# peripherals.net
KiCad netlist of a schematic drawn in Altium Designer
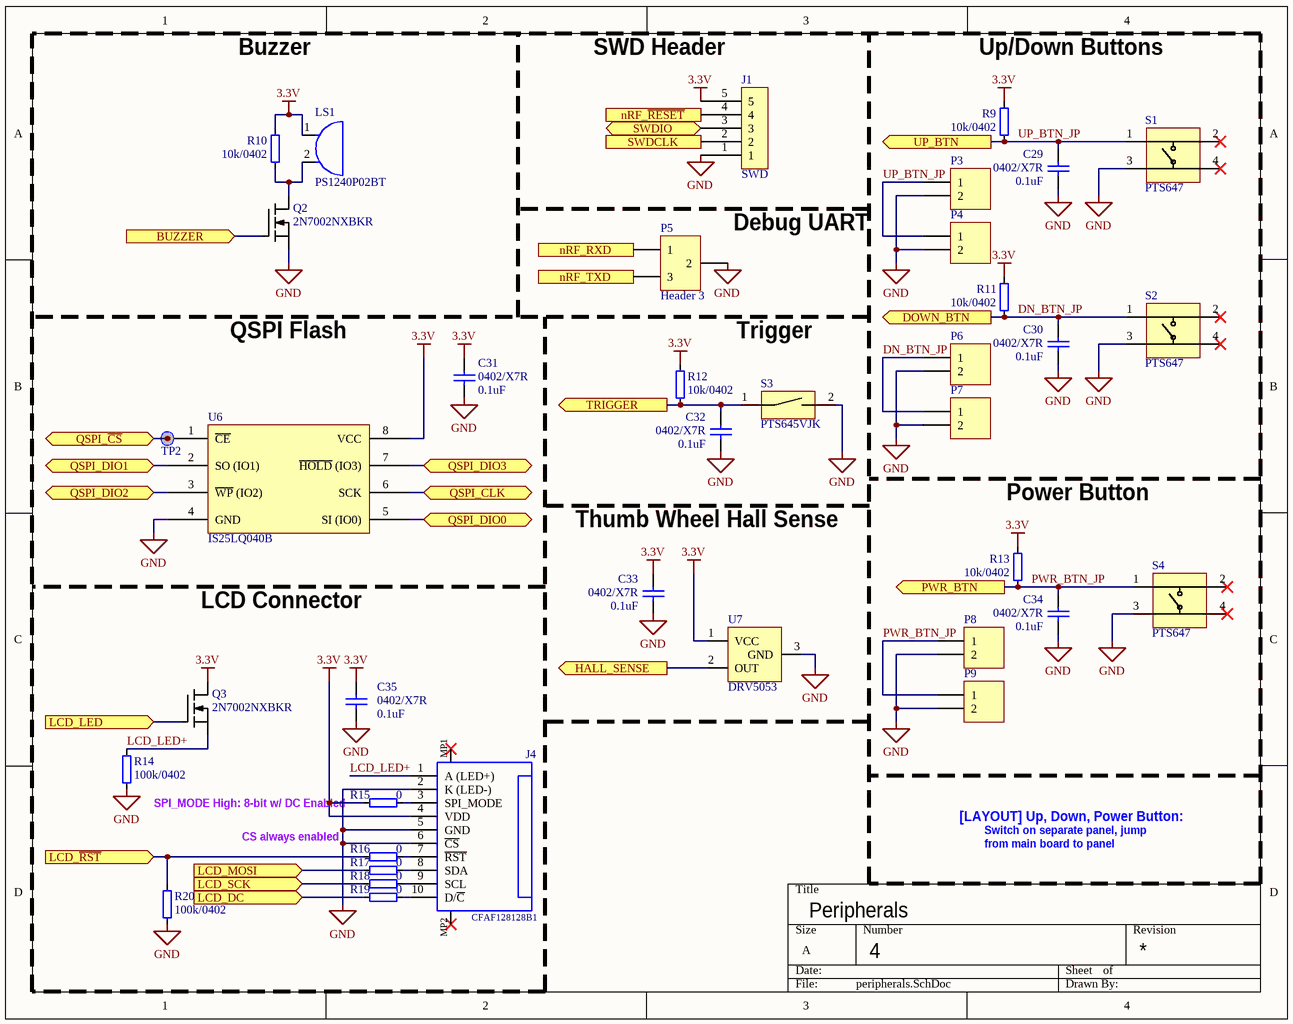
[diagram p0: peripherals.SchDoc]

(export (version "E")
  (design (tool "Eeschema 10.0.6"))
  (components
    (comp (ref "C29")
      (value "0402/X7R")
      (footprint "CAPC1005X04L")
      (description "Capacitor")
      (fields (field (name "ALTIUM_VALUE") "0.1uF") (field (name "PUBLISHER") "Altium Limited"))
      (libsource (lib "Miscellaneous Devices") (part "Cap"))
    )
    (comp (ref "C30")
      (value "0402/X7R")
      (footprint "CAPC1005X04L")
      (description "Capacitor")
      (fields (field (name "ALTIUM_VALUE") "0.1uF") (field (name "PUBLISHER") "Altium Limited"))
      (libsource (lib "Miscellaneous Devices") (part "Cap"))
    )
    (comp (ref "C31")
      (value "0402/X7R")
      (footprint "CAPC1005X04L")
      (description "Capacitor")
      (fields (field (name "ALTIUM_VALUE") "0.1uF") (field (name "PUBLISHER") "Altium Limited"))
      (libsource (lib "Miscellaneous Devices") (part "Cap"))
    )
    (comp (ref "C32")
      (value "0402/X7R")
      (footprint "CAPC1005X04L")
      (description "Capacitor")
      (fields (field (name "ALTIUM_VALUE") "0.1uF") (field (name "PUBLISHER") "Altium Limited"))
      (libsource (lib "Miscellaneous Devices") (part "Cap"))
    )
    (comp (ref "C33")
      (value "0402/X7R")
      (footprint "CAPC1005X04L")
      (description "Capacitor")
      (fields (field (name "ALTIUM_VALUE") "0.1uF") (field (name "PUBLISHER") "Altium Limited"))
      (libsource (lib "Miscellaneous Devices") (part "Cap"))
    )
    (comp (ref "C34")
      (value "0402/X7R")
      (footprint "CAPC1005X04L")
      (description "Capacitor")
      (fields (field (name "ALTIUM_VALUE") "0.1uF") (field (name "PUBLISHER") "Altium Limited"))
      (libsource (lib "Miscellaneous Devices") (part "Cap"))
    )
    (comp (ref "C35")
      (value "0402/X7R")
      (footprint "CAPC1005X04L")
      (description "Capacitor")
      (fields (field (name "ALTIUM_VALUE") "0.1uF") (field (name "PUBLISHER") "Altium Limited"))
      (libsource (lib "Miscellaneous Devices") (part "Cap"))
    )
    (comp (ref "J1") (value "SWD") (footprint "SWD 5-pin") (libsource (lib "remote") (part "Debug_Header")))
    (comp (ref "J4")
      (value "CFAF128128B1")
      (footprint "68711014022")
      (description "10-pin 0.5mm pitch FPC for CFAF128128B1 TFT LCD")
      (fields
        (field (name "PART NUMBER") "68711014022")
        (field (name "MANUFACTURER") "Wurth Elektronik")
        (field (name "PUBLISHER") "WurthElektronik")
      )
      (libsource (lib "remote") (part "CFAF128128B1-0145T"))
    )
    (comp (ref "LS1")
      (value "PS1240P02BT")
      (footprint "Passive Buzzer")
      (description "Buzzers Transducer, Externally Driven Piezo 3V  4kHz 60dB @ 3V, 10cm Through Hole PC Pins")
      (libsource (lib "remote") (part "PS1240P02BT"))
    )
    (comp (ref "P3")
      (value "UP")
      (footprint "HDR1X2")
      (description "Header, 2-Pin")
      (fields (field (name "PUBLISHER") "Altium Limited"))
      (libsource (lib "Miscellaneous Connectors") (part "Header 2"))
    )
    (comp (ref "P4")
      (value "UP")
      (footprint "HDR1X2")
      (description "Header, 2-Pin")
      (fields (field (name "PUBLISHER") "Altium Limited"))
      (libsource (lib "Miscellaneous Connectors") (part "Header 2"))
    )
    (comp (ref "P5")
      (value "Header 3")
      (footprint "UART")
      (description "Header, 3-Pin")
      (fields (field (name "PUBLISHER") "Altium Limited"))
      (libsource (lib "remote") (part "Header 3"))
    )
    (comp (ref "P6")
      (value "DOWN")
      (footprint "HDR1X2")
      (description "Header, 2-Pin")
      (fields (field (name "PUBLISHER") "Altium Limited"))
      (libsource (lib "Miscellaneous Connectors") (part "Header 2"))
    )
    (comp (ref "P7")
      (value "DOWN")
      (footprint "HDR1X2")
      (description "Header, 2-Pin")
      (fields (field (name "PUBLISHER") "Altium Limited"))
      (libsource (lib "Miscellaneous Connectors") (part "Header 2"))
    )
    (comp (ref "P8")
      (value "POWER")
      (footprint "HDR1X2")
      (description "Header, 2-Pin")
      (fields (field (name "PUBLISHER") "Altium Limited"))
      (libsource (lib "Miscellaneous Connectors") (part "Header 2"))
    )
    (comp (ref "P9")
      (value "POWER")
      (footprint "HDR1X2")
      (description "Header, 2-Pin")
      (fields (field (name "PUBLISHER") "Altium Limited"))
      (libsource (lib "Miscellaneous Connectors") (part "Header 2"))
    )
    (comp (ref "Q2")
      (value "2N7002NXBKR")
      (footprint "SOT190P230X110-3N")
      (description "N-Channel 60V 270mA (Ta), 330mA (Tc) 310mW (Ta), 1.67W (Tc) Surface Mount TO-236AB")
      (libsource (lib "remote") (part "2N7002NXBKR"))
    )
    (comp (ref "Q3")
      (value "2N7002NXBKR")
      (footprint "SOT190P230X110-3N")
      (description "N-Channel 60V 270mA (Ta), 330mA (Tc) 310mW (Ta), 1.67W (Tc) Surface Mount TO-236AB")
      (libsource (lib "remote") (part "2N7002NXBKR"))
    )
    (comp (ref "R9")
      (value "10k/0402")
      (footprint "0402")
      (description "Resistor")
      (fields (field (name "PUBLISHER") "Altium Limited"))
      (libsource (lib "remote") (part "Resistor"))
    )
    (comp (ref "R10")
      (value "10k/0402")
      (footprint "0402")
      (description "Resistor")
      (fields (field (name "PUBLISHER") "Altium Limited"))
      (libsource (lib "remote") (part "Resistor"))
    )
    (comp (ref "R11")
      (value "10k/0402")
      (footprint "0402")
      (description "Resistor")
      (fields (field (name "PUBLISHER") "Altium Limited"))
      (libsource (lib "remote") (part "Resistor"))
    )
    (comp (ref "R12")
      (value "10k/0402")
      (footprint "0402")
      (description "Resistor")
      (fields (field (name "PUBLISHER") "Altium Limited"))
      (libsource (lib "remote") (part "Resistor"))
    )
    (comp (ref "R13")
      (value "10k/0402")
      (footprint "0402")
      (description "Resistor")
      (fields (field (name "PUBLISHER") "Altium Limited"))
      (libsource (lib "remote") (part "Resistor"))
    )
    (comp (ref "R14")
      (value "100k/0402")
      (footprint "0402")
      (description "Resistor")
      (fields (field (name "PUBLISHER") "Altium Limited"))
      (libsource (lib "remote") (part "Resistor"))
    )
    (comp (ref "R15")
      (value "0")
      (footprint "J1-0603")
      (fields (field (name "Comment") "Resistor") (field (name "PUBLISHER") "Altium Limited"))
      (libsource (lib "") (part "Resistor_1"))
    )
    (comp (ref "R16")
      (value "0")
      (footprint "J1-0603")
      (fields (field (name "Comment") "Resistor") (field (name "PUBLISHER") "Altium Limited"))
      (libsource (lib "") (part "Resistor_1"))
    )
    (comp (ref "R17")
      (value "0")
      (footprint "J1-0603")
      (fields (field (name "Comment") "Resistor") (field (name "PUBLISHER") "Altium Limited"))
      (libsource (lib "") (part "Resistor_1"))
    )
    (comp (ref "R18")
      (value "0")
      (footprint "J1-0603")
      (fields (field (name "Comment") "Resistor") (field (name "PUBLISHER") "Altium Limited"))
      (libsource (lib "") (part "Resistor_1"))
    )
    (comp (ref "R19")
      (value "0")
      (footprint "J1-0603")
      (fields (field (name "Comment") "Resistor") (field (name "PUBLISHER") "Altium Limited"))
      (libsource (lib "") (part "Resistor_1"))
    )
    (comp (ref "R20")
      (value "100k/0402")
      (footprint "0402")
      (description "Resistor")
      (fields (field (name "PUBLISHER") "Altium Limited"))
      (libsource (lib "remote") (part "Resistor"))
    )
    (comp (ref "S1")
      (value "PTS647")
      (footprint "SW_CK_ PTS647SK50SMTR2LFS")
      (description "Tactile Switch SPST-NO Top Actuated Surface Mount")
      (libsource (lib "remote") (part "SW_CK_ PTS647SK50SMTR2LFS"))
    )
    (comp (ref "S2")
      (value "PTS647")
      (footprint "SW_CK_ PTS647SK50SMTR2LFS")
      (description "Tactile Switch SPST-NO Top Actuated Surface Mount")
      (libsource (lib "remote") (part "SW_CK_ PTS647SK50SMTR2LFS"))
    )
    (comp (ref "S3")
      (value "PTS645VJK")
      (footprint "SW_CK_PTS645VJK612LFS")
      (description "Tactile Switch SPST-NO Side Actuated Through Hole, Right Angle")
      (libsource (lib "remote") (part "SW_CK_PTS645VJK612LFS"))
    )
    (comp (ref "S4")
      (value "PTS647")
      (footprint "SW_CK_ PTS647SK50SMTR2LFS")
      (description "Tactile Switch SPST-NO Top Actuated Surface Mount")
      (libsource (lib "remote") (part "SW_CK_ PTS647SK50SMTR2LFS"))
    )
    (comp (ref "TP2")
      (value "TP_Via")
      (footprint "TP_Via")
      (description "Test point as a via")
      (libsource (lib "remote") (part "TP_Via"))
    )
    (comp (ref "U6")
      (value "IS25LQ040B")
      (footprint "SOIC127P600X175-8N")
      (description "FLASH - NOR Memory IC 4Mb (512K x 8) SPI - Quad I/O 104MHz  8-SOIC")
      (libsource (lib "remote") (part "IS25LQ040B-JNLE"))
    )
    (comp (ref "U7")
      (value "DRV5053")
      (footprint "SOT190P237X112-3N")
      (description "Hall Effect Sensor Single Axis SOT-23-3")
      (libsource (lib "remote") (part "DRV5053VAQDBZR"))
    )
  )
  (nets
    (net (code "1") (name "/BUZZER") (class "Default")
      (node (ref "Q2") (pin "1") (pinfunction "G_1") (pintype "passive"))
    )
    (net (code "2") (name "/DN_BTN_JP") (class "Default")
      (node (ref "C30") (pin "2") (pinfunction "2_2") (pintype "passive"))
      (node (ref "P6") (pin "1") (pinfunction "1_1") (pintype "passive"))
      (node (ref "P7") (pin "1") (pinfunction "1_1") (pintype "passive"))
      (node (ref "R11") (pin "1") (pinfunction "1_1") (pintype "passive"))
      (node (ref "S2") (pin "1") (pinfunction "1_1") (pintype "passive"))
    )
    (net (code "3") (name "/HALL_SENSE") (class "Default")
      (node (ref "U7") (pin "2") (pinfunction "OUT_2") (pintype "passive"))
    )
    (net (code "4") (name "/LCD_DC") (class "Default")
      (node (ref "R19") (pin "2") (pinfunction "2_2") (pintype "passive"))
    )
    (net (code "5") (name "/LCD_LED") (class "Default")
      (node (ref "Q3") (pin "1") (pinfunction "G_1") (pintype "passive"))
    )
    (net (code "6") (name "/LCD_LED+") (class "Default")
      (node (ref "J4") (pin "1") (pinfunction "A_(LED+)_1") (pintype "passive"))
      (node (ref "Q3") (pin "2") (pinfunction "S_2") (pintype "passive"))
      (node (ref "R14") (pin "2") (pinfunction "2_2") (pintype "passive"))
    )
    (net (code "7") (name "/LCD_MOSI") (class "Default")
      (node (ref "R17") (pin "2") (pinfunction "2_2") (pintype "passive"))
    )
    (net (code "8") (name "/LCD_SCK") (class "Default")
      (node (ref "R18") (pin "2") (pinfunction "2_2") (pintype "passive"))
    )
    (net (code "9") (name "/LCD_~{RST}") (class "Default")
      (node (ref "R16") (pin "2") (pinfunction "2_2") (pintype "passive"))
      (node (ref "R20") (pin "2") (pinfunction "2_2") (pintype "passive"))
    )
    (net (code "10") (name "/PWR_BTN_JP") (class "Default")
      (node (ref "C34") (pin "2") (pinfunction "2_2") (pintype "passive"))
      (node (ref "P8") (pin "1") (pinfunction "1_1") (pintype "passive"))
      (node (ref "P9") (pin "1") (pinfunction "1_1") (pintype "passive"))
      (node (ref "R13") (pin "1") (pinfunction "1_1") (pintype "passive"))
      (node (ref "S4") (pin "1") (pinfunction "1_1") (pintype "passive"))
    )
    (net (code "11") (name "/QSPI_CLK") (class "Default")
      (node (ref "U6") (pin "6") (pinfunction "SCK_6") (pintype "passive"))
    )
    (net (code "12") (name "/QSPI_DIO0") (class "Default")
      (node (ref "U6") (pin "5") (pinfunction "SI_(IO0)_5") (pintype "passive"))
    )
    (net (code "13") (name "/QSPI_DIO1") (class "Default")
      (node (ref "U6") (pin "2") (pinfunction "SO_(IO1)_2") (pintype "passive"))
    )
    (net (code "14") (name "/QSPI_DIO2") (class "Default")
      (node (ref "U6") (pin "3") (pinfunction "~{WP}_(IO2)_3") (pintype "passive"))
    )
    (net (code "15") (name "/QSPI_DIO3") (class "Default")
      (node (ref "U6") (pin "7") (pinfunction "~{HOLD}_(IO3)_7") (pintype "passive"))
    )
    (net (code "16") (name "/QSPI_~{CS}") (class "Default")
      (node (ref "TP2") (pin "1") (pinfunction "1_1") (pintype "passive"))
      (node (ref "U6") (pin "1") (pinfunction "~{CE}_1") (pintype "passive"))
    )
    (net (code "17") (name "/SWDCLK") (class "Default")
      (node (ref "J1") (pin "2") (pinfunction "2_2") (pintype "passive"))
    )
    (net (code "18") (name "/SWDIO") (class "Default")
      (node (ref "J1") (pin "3") (pinfunction "3_3") (pintype "passive"))
    )
    (net (code "19") (name "/TRIGGER") (class "Default")
      (node (ref "C32") (pin "2") (pinfunction "2_2") (pintype "passive"))
      (node (ref "R12") (pin "1") (pinfunction "1_1") (pintype "passive"))
      (node (ref "S3") (pin "1") (pinfunction "1_1") (pintype "passive"))
    )
    (net (code "20") (name "/UP_BTN_JP") (class "Default")
      (node (ref "C29") (pin "2") (pinfunction "2_2") (pintype "passive"))
      (node (ref "P3") (pin "1") (pinfunction "1_1") (pintype "passive"))
      (node (ref "P4") (pin "1") (pinfunction "1_1") (pintype "passive"))
      (node (ref "R9") (pin "1") (pinfunction "1_1") (pintype "passive"))
      (node (ref "S1") (pin "1") (pinfunction "1_1") (pintype "passive"))
    )
    (net (code "21") (name "/nRF_RXD") (class "Default")
      (node (ref "P5") (pin "1") (pinfunction "1_1") (pintype "passive"))
    )
    (net (code "22") (name "/nRF_TXD") (class "Default")
      (node (ref "P5") (pin "3") (pinfunction "3_3") (pintype "passive"))
    )
    (net (code "23") (name "/nRF_~{RESET}") (class "Default")
      (node (ref "J1") (pin "4") (pinfunction "4_4") (pintype "passive"))
    )
    (net (code "24") (name "3.3V") (class "Default")
      (node (ref "C31") (pin "2") (pinfunction "2_2") (pintype "passive"))
      (node (ref "C33") (pin "2") (pinfunction "2_2") (pintype "passive"))
      (node (ref "C35") (pin "2") (pinfunction "2_2") (pintype "passive"))
      (node (ref "J1") (pin "5") (pinfunction "5_5") (pintype "passive"))
      (node (ref "J4") (pin "4") (pinfunction "VDD_4") (pintype "passive"))
      (node (ref "LS1") (pin "1") (pinfunction "1_1") (pintype "passive"))
      (node (ref "Q3") (pin "3") (pinfunction "D_3") (pintype "passive"))
      (node (ref "R10") (pin "2") (pinfunction "2_2") (pintype "passive"))
      (node (ref "R11") (pin "2") (pinfunction "2_2") (pintype "passive"))
      (node (ref "R12") (pin "2") (pinfunction "2_2") (pintype "passive"))
      (node (ref "R13") (pin "2") (pinfunction "2_2") (pintype "passive"))
      (node (ref "R15") (pin "2") (pinfunction "2_2") (pintype "passive"))
      (node (ref "R9") (pin "2") (pinfunction "2_2") (pintype "passive"))
      (node (ref "U6") (pin "8") (pinfunction "VCC_8") (pintype "passive"))
      (node (ref "U7") (pin "1") (pinfunction "VCC_1") (pintype "passive"))
    )
    (net (code "25") (name "GND") (class "Default")
      (node (ref "C29") (pin "1") (pinfunction "1_1") (pintype "passive"))
      (node (ref "C30") (pin "1") (pinfunction "1_1") (pintype "passive"))
      (node (ref "C31") (pin "1") (pinfunction "1_1") (pintype "passive"))
      (node (ref "C32") (pin "1") (pinfunction "1_1") (pintype "passive"))
      (node (ref "C33") (pin "1") (pinfunction "1_1") (pintype "passive"))
      (node (ref "C34") (pin "1") (pinfunction "1_1") (pintype "passive"))
      (node (ref "C35") (pin "1") (pinfunction "1_1") (pintype "passive"))
      (node (ref "J1") (pin "1") (pinfunction "1_1") (pintype "passive"))
      (node (ref "J4") (pin "2") (pinfunction "K_(LED-)_2") (pintype "passive"))
      (node (ref "J4") (pin "5") (pinfunction "GND_5") (pintype "passive"))
      (node (ref "J4") (pin "6") (pinfunction "~{CS}_6") (pintype "passive"))
      (node (ref "P3") (pin "2") (pinfunction "2_2") (pintype "passive"))
      (node (ref "P4") (pin "2") (pinfunction "2_2") (pintype "passive"))
      (node (ref "P5") (pin "2") (pinfunction "2_2") (pintype "passive"))
      (node (ref "P6") (pin "2") (pinfunction "2_2") (pintype "passive"))
      (node (ref "P7") (pin "2") (pinfunction "2_2") (pintype "passive"))
      (node (ref "P8") (pin "2") (pinfunction "2_2") (pintype "passive"))
      (node (ref "P9") (pin "2") (pinfunction "2_2") (pintype "passive"))
      (node (ref "Q2") (pin "2") (pinfunction "S_2") (pintype "passive"))
      (node (ref "R14") (pin "1") (pinfunction "1_1") (pintype "passive"))
      (node (ref "R20") (pin "1") (pinfunction "1_1") (pintype "passive"))
      (node (ref "S1") (pin "3") (pinfunction "3_3") (pintype "passive"))
      (node (ref "S2") (pin "3") (pinfunction "3_3") (pintype "passive"))
      (node (ref "S3") (pin "2") (pinfunction "2_2") (pintype "passive"))
      (node (ref "S4") (pin "3") (pinfunction "3_3") (pintype "passive"))
      (node (ref "U6") (pin "4") (pinfunction "GND_4") (pintype "passive"))
      (node (ref "U7") (pin "3") (pinfunction "GND_3") (pintype "passive"))
    )
    (net (code "26") (name "Net-(J4-D{slash}~{C})") (class "Default")
      (node (ref "J4") (pin "10") (pinfunction "D/~{C}_10") (pintype "passive"))
      (node (ref "R19") (pin "1") (pinfunction "1_1") (pintype "passive"))
    )
    (net (code "27") (name "Net-(J4-SCL)") (class "Default")
      (node (ref "J4") (pin "9") (pinfunction "SCL_9") (pintype "passive"))
      (node (ref "R18") (pin "1") (pinfunction "1_1") (pintype "passive"))
    )
    (net (code "28") (name "Net-(J4-SDA)") (class "Default")
      (node (ref "J4") (pin "8") (pinfunction "SDA_8") (pintype "passive"))
      (node (ref "R17") (pin "1") (pinfunction "1_1") (pintype "passive"))
    )
    (net (code "29") (name "Net-(J4-SPI_MODE)") (class "Default")
      (node (ref "J4") (pin "3") (pinfunction "SPI_MODE_3") (pintype "passive"))
      (node (ref "R15") (pin "1") (pinfunction "1_1") (pintype "passive"))
    )
    (net (code "30") (name "Net-(J4-~{RST})") (class "Default")
      (node (ref "J4") (pin "7") (pinfunction "~{RST}_7") (pintype "passive"))
      (node (ref "R16") (pin "1") (pinfunction "1_1") (pintype "passive"))
    )
    (net (code "31") (name "Net-(Q2-D)") (class "Default")
      (node (ref "LS1") (pin "2") (pinfunction "2_2") (pintype "passive"))
      (node (ref "Q2") (pin "3") (pinfunction "D_3") (pintype "passive"))
      (node (ref "R10") (pin "1") (pinfunction "1_1") (pintype "passive"))
    )
    (net (code "32") (name "unconnected-(J4-PadMP1)") (class "Default")
      (node (ref "J4") (pin "MP1") (pinfunction "MP1_MP1") (pintype "passive+no_connect"))
    )
    (net (code "33") (name "unconnected-(J4-PadMP2)") (class "Default")
      (node (ref "J4") (pin "MP2") (pinfunction "MP2_MP2") (pintype "passive+no_connect"))
    )
    (net (code "34") (name "unconnected-(S1-Pad2)") (class "Default")
      (node (ref "S1") (pin "2") (pinfunction "2_2") (pintype "passive+no_connect"))
    )
    (net (code "35") (name "unconnected-(S1-Pad4)") (class "Default")
      (node (ref "S1") (pin "4") (pinfunction "4_4") (pintype "passive+no_connect"))
    )
    (net (code "36") (name "unconnected-(S2-Pad2)") (class "Default")
      (node (ref "S2") (pin "2") (pinfunction "2_2") (pintype "passive+no_connect"))
    )
    (net (code "37") (name "unconnected-(S2-Pad4)") (class "Default")
      (node (ref "S2") (pin "4") (pinfunction "4_4") (pintype "passive+no_connect"))
    )
    (net (code "38") (name "unconnected-(S4-Pad2)") (class "Default")
      (node (ref "S4") (pin "2") (pinfunction "2_2") (pintype "passive+no_connect"))
    )
    (net (code "39") (name "unconnected-(S4-Pad4)") (class "Default")
      (node (ref "S4") (pin "4") (pinfunction "4_4") (pintype "passive+no_connect"))
    )
  )
)
